# mapleCUx_large_400-001.net
KiCad netlist of a schematic drawn in EAGLE
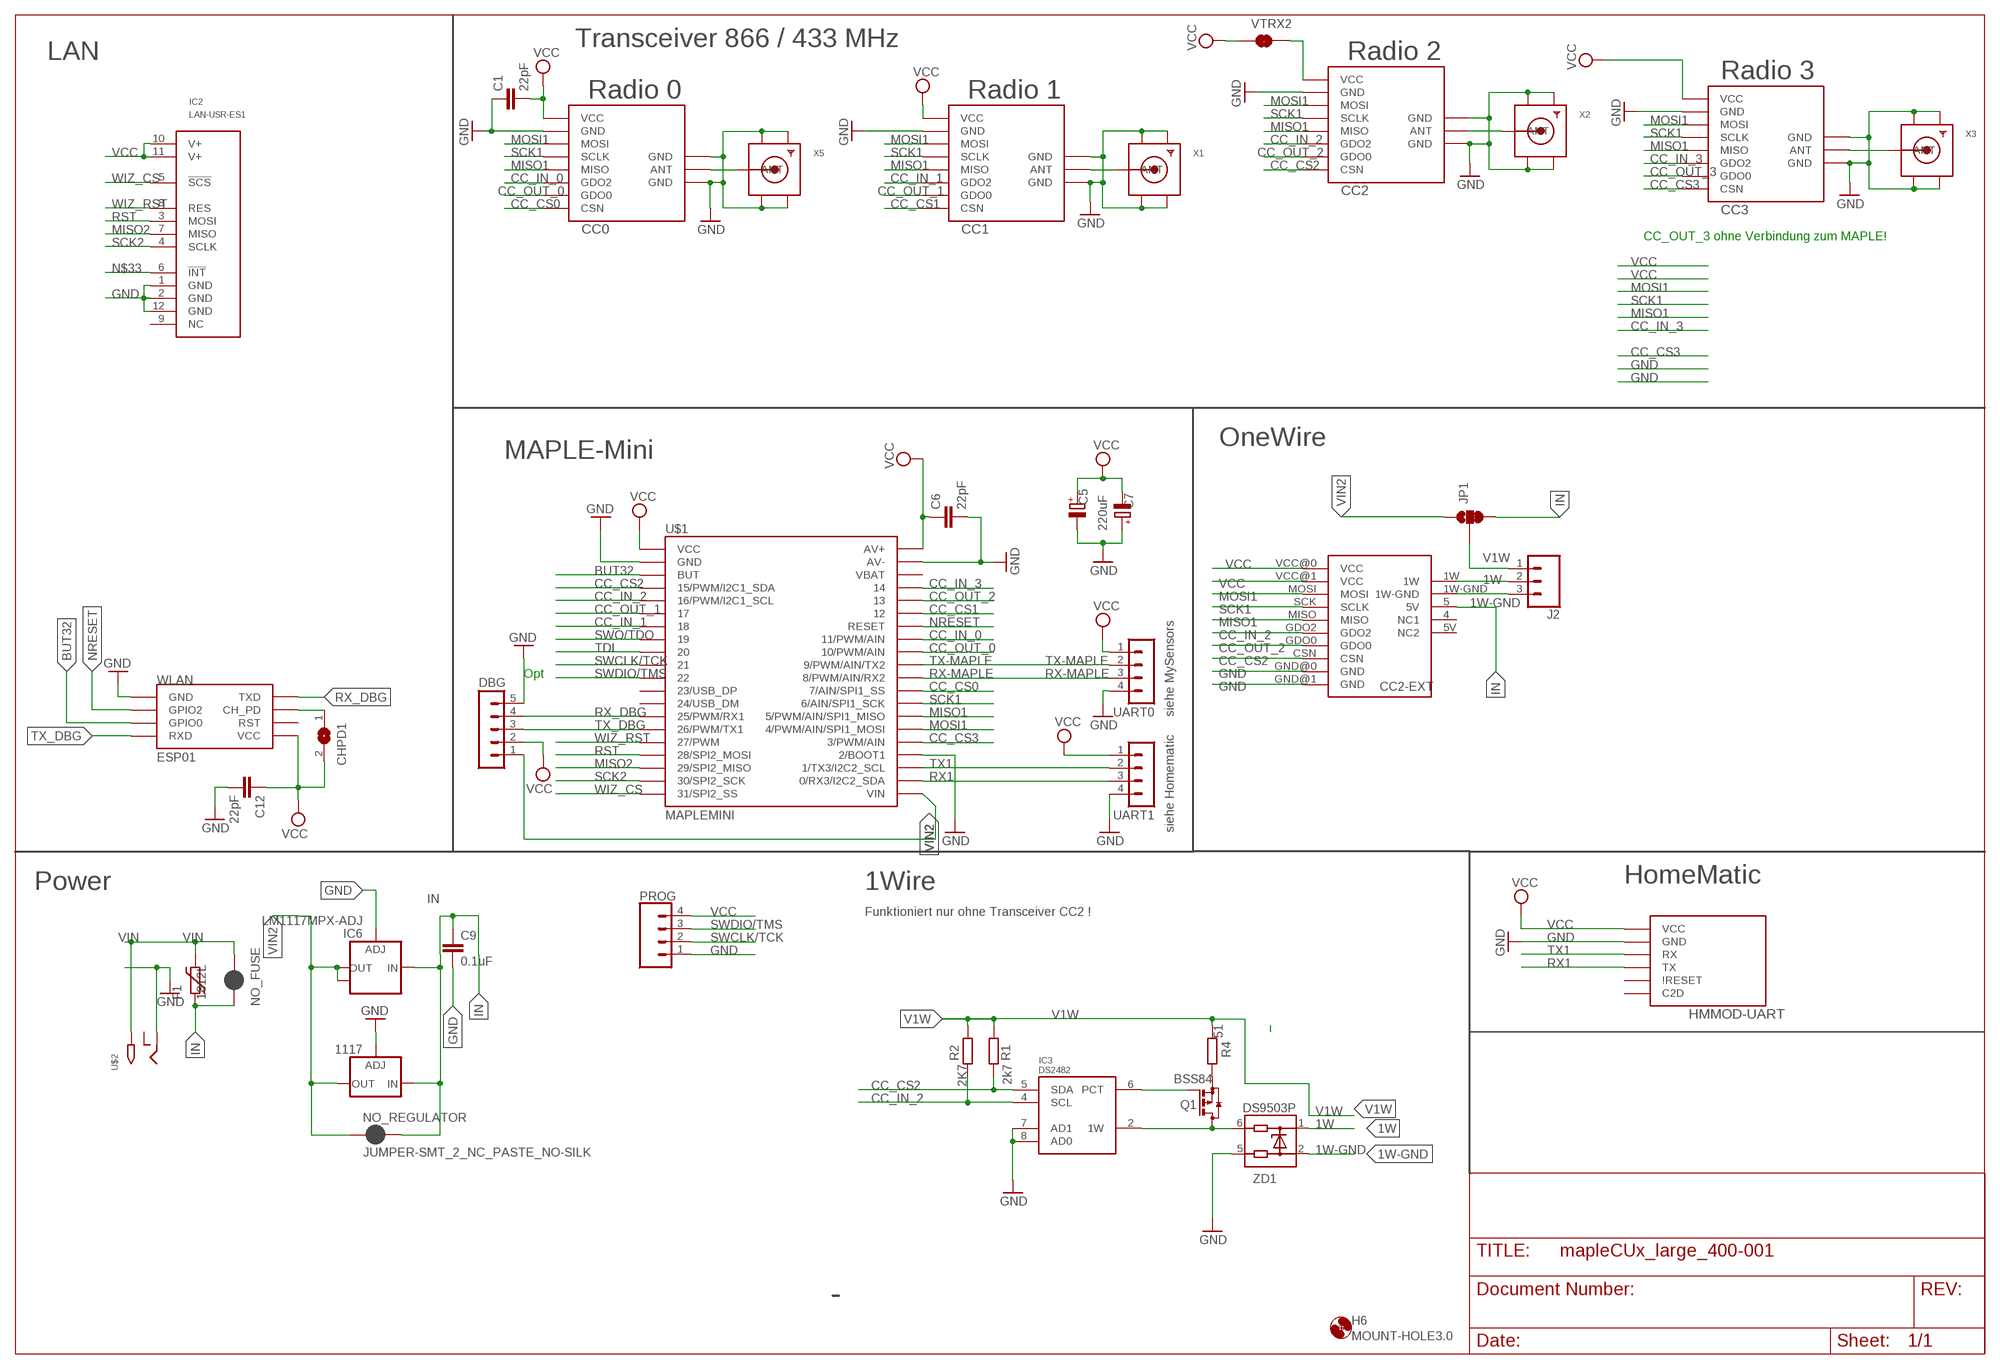
[diagram p0: schematic, sheet 1]

(export (version "E")
  (design (tool "Eeschema 10.0.6"))
  (components
    (comp (ref "1117")
      (value "LD117ADT50TR")
      (footprint "eagle-import:DPACK")
      (libsource (lib "eagle-import") (part "LD117A?DT50TR"))
    )
    (comp (ref "C1")
      (value "22pF")
      (footprint "eagle-import:C0805")
      (libsource (lib "eagle-import") (part "C-EUC0805"))
    )
    (comp (ref "C5")
      (value "220uF")
      (footprint "eagle-import:E5-8,5")
      (libsource (lib "eagle-import") (part "CPOL-EUE5-8.5"))
    )
    (comp (ref "C6")
      (value "22pF")
      (footprint "eagle-import:C0805")
      (libsource (lib "eagle-import") (part "C-EUC0805"))
    )
    (comp (ref "C7")
      (value "CPOL-EUSMCE")
      (footprint "eagle-import:SMC_E")
      (libsource (lib "eagle-import") (part "rcl_334_CPOL-EUSMCE"))
    )
    (comp (ref "C9")
      (value "0.1uF")
      (footprint "eagle-import:C1206")
      (libsource (lib "eagle-import") (part "C-EUC1206"))
    )
    (comp (ref "C12")
      (value "22pF")
      (footprint "eagle-import:C0805")
      (libsource (lib "eagle-import") (part "C-EUC0805"))
    )
    (comp (ref "CC0")
      (value "CC1101")
      (footprint "eagle-import:CC1101_MODULE1_SMD")
      (libsource (lib "eagle-import") (part "CC1101_MODULE1SMD"))
    )
    (comp (ref "CC1")
      (value "CC1101_MODULE1SMD")
      (footprint "eagle-import:CC1101_MODULE1_SMD")
      (libsource (lib "eagle-import") (part "CC1101_MODULE1SMD"))
    )
    (comp (ref "CC2")
      (value "CC1101_MODULE1SMD")
      (footprint "eagle-import:CC1101_MODULE1_SMD")
      (libsource (lib "eagle-import") (part "CC1101_MODULE1SMD"))
    )
    (comp (ref "CC2-EXT")
      (value "ONEWIRE-MODULE")
      (footprint "eagle-import:ONEWIRE_CC1101_MODULE3_DIL")
      (libsource (lib "eagle-import") (part "ONEWIRE-MODULE"))
    )
    (comp (ref "CC3")
      (value "CC1101_MODULE1SMD")
      (footprint "eagle-import:CC1101_MODULE1_SMD")
      (libsource (lib "eagle-import") (part "CC1101_MODULE1SMD"))
    )
    (comp (ref "CHPD1")
      (value "SJ")
      (footprint "eagle-import:SJ")
      (libsource (lib "eagle-import") (part "SJ"))
    )
    (comp (ref "DBG")
      (value "MA05-1")
      (footprint "eagle-import:MA05-1")
      (libsource (lib "eagle-import") (part "MA05-1"))
    )
    (comp (ref "F1")
      (value "1812L")
      (footprint "eagle-import:1812L")
      (libsource (lib "eagle-import") (part "1812L"))
    )
    (comp (ref "H6")
      (value "MOUNT-HOLE3.0")
      (footprint "eagle-import:3,0")
      (libsource (lib "eagle-import") (part "MOUNT-HOLE3.0"))
    )
    (comp (ref "HMMOD-UART")
      (value "HM-MOD-UARTDIL")
      (footprint "eagle-import:HM-MOD-UART-DIL")
      (libsource (lib "eagle-import") (part "HM-MOD-UARTDIL"))
    )
    (comp (ref "IC2")
      (value "LAN-USR-ES1")
      (footprint "eagle-import:USR-ES1")
      (libsource (lib "eagle-import") (part "LAN-USR-ES1"))
    )
    (comp (ref "IC3")
      (value "DS2482")
      (footprint "eagle-import:SO08")
      (libsource (lib "eagle-import") (part "DS2482-100S"))
    )
    (comp (ref "IC6")
      (value "LM1117MPX-ADJ")
      (footprint "eagle-import:SOT223")
      (libsource (lib "eagle-import") (part "LM1117MPX-ADJ"))
    )
    (comp (ref "J2")
      (value "CONN_03LONGPADS")
      (footprint "eagle-import:1X03_LONGPADS")
      (libsource (lib "eagle-import") (part "CONN_03LONGPADS"))
    )
    (comp (ref "JP1")
      (value "JUMPER-SMT_3_1-NC_TRACE_SILK")
      (footprint "eagle-import:SMT-JUMPER_3_1-NC_TRACE_SILK")
      (libsource (lib "eagle-import") (part "JUMPER-SMT_3_1-NC_TRACE_SILK"))
    )
    (comp (ref "NO_FUSE")
      (value "JUMPER-SMT_2_NC_PASTE_NO-SILK")
      (footprint "eagle-import:SMT-JUMPER_2_NC_PASTE_NO-SILK")
      (libsource (lib "eagle-import") (part "JUMPER-SMT_2_NC_PASTE_NO-SILK"))
    )
    (comp (ref "NO_REGULATOR")
      (value "JUMPER-SMT_2_NC_PASTE_NO-SILK")
      (footprint "eagle-import:SMT-JUMPER_2_NC_PASTE_NO-SILK")
      (libsource (lib "eagle-import") (part "JUMPER-SMT_2_NC_PASTE_NO-SILK"))
    )
    (comp (ref "PROG")
      (value "CONN_04LOCK")
      (footprint "eagle-import:1X04_LOCK")
      (libsource (lib "eagle-import") (part "CONN_04LOCK"))
    )
    (comp (ref "Q1")
      (value "BSS84")
      (footprint "eagle-import:SOT23")
      (libsource (lib "eagle-import") (part "BSS84"))
    )
    (comp (ref "R1")
      (value "2k7")
      (footprint "eagle-import:R0805")
      (libsource (lib "eagle-import") (part "R-EU_R0805"))
    )
    (comp (ref "R2")
      (value "2K7")
      (footprint "eagle-import:R0805")
      (libsource (lib "eagle-import") (part "R-EU_R0805"))
    )
    (comp (ref "R4")
      (value "51")
      (footprint "eagle-import:R0805")
      (libsource (lib "eagle-import") (part "R-EU_R0805"))
    )
    (comp (ref "U$1")
      (value "MAPLEMINI")
      (footprint "eagle-import:20-DIP")
      (libsource (lib "eagle-import") (part "MAPLEMINI"))
    )
    (comp (ref "U$2")
      (value "2.1MMJACKTHM")
      (footprint "eagle-import:PJ-102A")
      (libsource (lib "eagle-import") (part "2.1MMJACKTHM"))
    )
    (comp (ref "UART0")
      (value "MA04-1")
      (footprint "eagle-import:MA04-1")
      (libsource (lib "eagle-import") (part "MA04-1"))
    )
    (comp (ref "UART1")
      (value "MA04-1")
      (footprint "eagle-import:MA04-1")
      (libsource (lib "eagle-import") (part "MA04-1"))
    )
    (comp (ref "VTRX2")
      (value "JUMPER-SMT_2_NC_TRACE_SILK")
      (footprint "eagle-import:SMT-JUMPER_2_NC_TRACE_SILK")
      (libsource (lib "eagle-import") (part "JUMPER-SMT_2_NC_TRACE_SILK"))
    )
    (comp (ref "WLAN")
      (value "ESP01")
      (footprint "eagle-import:ESP01")
      (libsource (lib "eagle-import") (part "ESP01"))
    )
    (comp (ref "X1")
      (value "SMACONNECTOR_EDGE")
      (footprint "eagle-import:SMA_EDGELAUNCH")
      (libsource (lib "eagle-import") (part "SMACONNECTOR_EDGE"))
    )
    (comp (ref "X2")
      (value "SMACONNECTOR_EDGE")
      (footprint "eagle-import:SMA_EDGELAUNCH")
      (libsource (lib "eagle-import") (part "SMACONNECTOR_EDGE"))
    )
    (comp (ref "X3")
      (value "SMACONNECTOR_EDGE")
      (footprint "eagle-import:SMA_EDGELAUNCH")
      (libsource (lib "eagle-import") (part "SMACONNECTOR_EDGE"))
    )
    (comp (ref "X5")
      (value "SMACONNECTOR_EDGE")
      (footprint "eagle-import:SMA_EDGELAUNCH")
      (libsource (lib "eagle-import") (part "SMACONNECTOR_EDGE"))
    )
    (comp (ref "ZD1")
      (value "DS9503P")
      (footprint "eagle-import:TSOC6")
      (libsource (lib "eagle-import") (part "DS9503P"))
    )
  )
  (nets
    (net (code "1") (name "/CC_CS0") (class "Default")
      (node (ref "CC0") (pin "CSN") (pinfunction "CSN_CSN") (pintype "bidirectional"))
      (node (ref "U$1") (pin "29") (pinfunction "7/AIN/SPI1_SS_29") (pintype "bidirectional"))
    )
    (net (code "2") (name "/CC_CS1") (class "Default")
      (node (ref "CC1") (pin "CSN") (pinfunction "CSN_CSN") (pintype "bidirectional"))
      (node (ref "U$1") (pin "35") (pinfunction "12_35") (pintype "bidirectional"))
    )
    (net (code "3") (name "/CC_CS2") (class "Default")
      (node (ref "CC2") (pin "CSN") (pinfunction "CSN_CSN") (pintype "bidirectional"))
      (node (ref "CC2-EXT") (pin "CSN") (pinfunction "CSN_CSN") (pintype "bidirectional"))
      (node (ref "IC3") (pin "5") (pinfunction "SDA_5") (pintype "bidirectional"))
      (node (ref "R1") (pin "2") (pinfunction "2_2") (pintype "passive"))
      (node (ref "U$1") (pin "4") (pinfunction "15/PWM/I2C1_SDA_4") (pintype "bidirectional"))
    )
    (net (code "4") (name "/CC_CS3") (class "Default")
      (node (ref "CC3") (pin "CSN") (pinfunction "CSN_CSN") (pintype "bidirectional"))
      (node (ref "U$1") (pin "25") (pinfunction "3/PWM/AIN_25") (pintype "bidirectional"))
    )
    (net (code "5") (name "/CC_IN_0") (class "Default")
      (node (ref "CC0") (pin "GDO2") (pinfunction "GDO2_GDO2") (pintype "bidirectional"))
      (node (ref "U$1") (pin "33") (pinfunction "11/PWM/AIN_33") (pintype "bidirectional"))
    )
    (net (code "6") (name "/CC_IN_1") (class "Default")
      (node (ref "CC1") (pin "GDO2") (pinfunction "GDO2_GDO2") (pintype "bidirectional"))
      (node (ref "U$1") (pin "7") (pinfunction "18_7") (pintype "bidirectional"))
    )
    (net (code "7") (name "/CC_IN_2") (class "Default")
      (node (ref "CC2") (pin "GDO2") (pinfunction "GDO2_GDO2") (pintype "bidirectional"))
      (node (ref "CC2-EXT") (pin "GDO2") (pinfunction "GDO2_GDO2") (pintype "bidirectional"))
      (node (ref "IC3") (pin "4") (pinfunction "SCL_4") (pintype "input"))
      (node (ref "R2") (pin "2") (pinfunction "2_2") (pintype "passive"))
      (node (ref "U$1") (pin "5") (pinfunction "16/PWM/I2C1_SCL_5") (pintype "bidirectional"))
    )
    (net (code "8") (name "/CC_IN_3") (class "Default")
      (node (ref "CC3") (pin "GDO2") (pinfunction "GDO2_GDO2") (pintype "bidirectional"))
      (node (ref "U$1") (pin "37") (pinfunction "14_37") (pintype "bidirectional"))
    )
    (net (code "9") (name "/CC_OUT_0") (class "Default")
      (node (ref "CC0") (pin "GDO0") (pinfunction "GDO0_GDO0") (pintype "bidirectional"))
      (node (ref "U$1") (pin "32") (pinfunction "10/PWM/AIN_32") (pintype "bidirectional"))
    )
    (net (code "10") (name "/CC_OUT_1") (class "Default")
      (node (ref "CC1") (pin "GDO0") (pinfunction "GDO0_GDO0") (pintype "bidirectional"))
      (node (ref "U$1") (pin "6") (pinfunction "17_6") (pintype "bidirectional"))
    )
    (net (code "11") (name "/CC_OUT_2") (class "Default")
      (node (ref "CC2") (pin "GDO0") (pinfunction "GDO0_GDO0") (pintype "bidirectional"))
      (node (ref "CC2-EXT") (pin "GDO0") (pinfunction "GDO0_GDO0") (pintype "bidirectional"))
      (node (ref "U$1") (pin "36") (pinfunction "13_36") (pintype "bidirectional"))
    )
    (net (code "12") (name "/CC_OUT_3") (class "Default")
      (node (ref "CC3") (pin "GDO0") (pinfunction "GDO0_GDO0") (pintype "bidirectional"))
    )
    (net (code "13") (name "/MISO1") (class "Default")
      (node (ref "CC0") (pin "MISO") (pinfunction "MISO_MISO") (pintype "bidirectional"))
      (node (ref "CC1") (pin "MISO") (pinfunction "MISO_MISO") (pintype "bidirectional"))
      (node (ref "CC2") (pin "MISO") (pinfunction "MISO_MISO") (pintype "bidirectional"))
      (node (ref "CC2-EXT") (pin "MISO") (pinfunction "MISO_MISO") (pintype "bidirectional"))
      (node (ref "CC3") (pin "MISO") (pinfunction "MISO_MISO") (pintype "bidirectional"))
      (node (ref "U$1") (pin "27") (pinfunction "5/PWM/AIN/SPI1_MISO_27") (pintype "bidirectional"))
    )
    (net (code "14") (name "/MISO2") (class "Default")
      (node (ref "IC2") (pin "7") (pinfunction "MISO_7") (pintype "bidirectional"))
      (node (ref "U$1") (pin "18") (pinfunction "29/SPI2_MISO_18") (pintype "bidirectional"))
    )
    (net (code "15") (name "/MOSI1") (class "Default")
      (node (ref "CC0") (pin "MOSI") (pinfunction "MOSI_MOSI") (pintype "bidirectional"))
      (node (ref "CC1") (pin "MOSI") (pinfunction "MOSI_MOSI") (pintype "bidirectional"))
      (node (ref "CC2") (pin "MOSI") (pinfunction "MOSI_MOSI") (pintype "bidirectional"))
      (node (ref "CC2-EXT") (pin "MOSI") (pinfunction "MOSI_MOSI") (pintype "bidirectional"))
      (node (ref "CC3") (pin "MOSI") (pinfunction "MOSI_MOSI") (pintype "bidirectional"))
      (node (ref "U$1") (pin "26") (pinfunction "4/PWM/AIN/SPI1_MOSI_26") (pintype "bidirectional"))
    )
    (net (code "16") (name "/N$33") (class "Default")
      (node (ref "IC2") (pin "6") (pinfunction "~{INT}_6") (pintype "output"))
    )
    (net (code "17") (name "/RST") (class "Default")
      (node (ref "IC2") (pin "3") (pinfunction "MOSI_3") (pintype "bidirectional"))
      (node (ref "U$1") (pin "17") (pinfunction "28/SPI2_MOSI_17") (pintype "bidirectional"))
    )
    (net (code "18") (name "/RX-MAPLE") (class "Default")
      (node (ref "U$1") (pin "30") (pinfunction "8/PWM/AIN/RX2_30") (pintype "bidirectional"))
      (node (ref "UART0") (pin "3") (pinfunction "3_3") (pintype "passive"))
    )
    (net (code "19") (name "/RX1") (class "Default")
      (node (ref "HMMOD-UART") (pin "5") (pinfunction "TX_5") (pintype "bidirectional"))
      (node (ref "U$1") (pin "22") (pinfunction "0/RX3/I2C2_SDA_22") (pintype "bidirectional"))
      (node (ref "UART1") (pin "3") (pinfunction "3_3") (pintype "passive"))
    )
    (net (code "20") (name "/SCK1") (class "Default")
      (node (ref "CC0") (pin "SCLK") (pinfunction "SCLK_SCLK") (pintype "bidirectional"))
      (node (ref "CC1") (pin "SCLK") (pinfunction "SCLK_SCLK") (pintype "bidirectional"))
      (node (ref "CC2") (pin "SCLK") (pinfunction "SCLK_SCLK") (pintype "bidirectional"))
      (node (ref "CC2-EXT") (pin "SCK") (pinfunction "SCLK_SCK") (pintype "bidirectional"))
      (node (ref "CC3") (pin "SCLK") (pinfunction "SCLK_SCLK") (pintype "bidirectional"))
      (node (ref "U$1") (pin "28") (pinfunction "6/AIN/SPI1_SCK_28") (pintype "bidirectional"))
    )
    (net (code "21") (name "/SCK2") (class "Default")
      (node (ref "IC2") (pin "4") (pinfunction "SCLK_4") (pintype "input"))
      (node (ref "U$1") (pin "19") (pinfunction "30/SPI2_SCK_19") (pintype "bidirectional"))
    )
    (net (code "22") (name "/SWCLK{slash}TCK") (class "Default")
      (node (ref "PROG") (pin "2") (pinfunction "2_2") (pintype "passive"))
      (node (ref "U$1") (pin "10") (pinfunction "21_10") (pintype "bidirectional"))
    )
    (net (code "23") (name "/SWDIO{slash}TMS") (class "Default")
      (node (ref "PROG") (pin "3") (pinfunction "3_3") (pintype "passive"))
      (node (ref "U$1") (pin "11") (pinfunction "22_11") (pintype "bidirectional"))
    )
    (net (code "24") (name "/SWO{slash}TDO") (class "Default")
      (node (ref "U$1") (pin "8") (pinfunction "19_8") (pintype "bidirectional"))
    )
    (net (code "25") (name "/TDI") (class "Default")
      (node (ref "U$1") (pin "9") (pinfunction "20_9") (pintype "bidirectional"))
    )
    (net (code "26") (name "/TX-MAPLE") (class "Default")
      (node (ref "U$1") (pin "31") (pinfunction "9/PWM/AIN/TX2_31") (pintype "bidirectional"))
      (node (ref "UART0") (pin "2") (pinfunction "2_2") (pintype "passive"))
    )
    (net (code "27") (name "/TX1") (class "Default")
      (node (ref "HMMOD-UART") (pin "6") (pinfunction "RX_6") (pintype "bidirectional"))
      (node (ref "U$1") (pin "23") (pinfunction "1/TX3/I2C2_SCL_23") (pintype "bidirectional"))
      (node (ref "UART1") (pin "2") (pinfunction "2_2") (pintype "passive"))
    )
    (net (code "28") (name "/VIN") (class "Default")
      (node (ref "F1") (pin "P$2") (pinfunction "2_P$2") (pintype "passive"))
      (node (ref "NO_FUSE") (pin "2") (pinfunction "2_2") (pintype "passive"))
      (node (ref "U$2") (pin "TIP") (pinfunction "TIP_TIP") (pintype "bidirectional"))
    )
    (net (code "29") (name "/WIZ_CS") (class "Default")
      (node (ref "IC2") (pin "5") (pinfunction "~{SCS}_5") (pintype "input"))
      (node (ref "U$1") (pin "20") (pinfunction "31/SPI2_SS_20") (pintype "bidirectional"))
    )
    (net (code "30") (name "/WIZ_RST") (class "Default")
      (node (ref "IC2") (pin "8") (pinfunction "RES_8") (pintype "input"))
      (node (ref "U$1") (pin "16") (pinfunction "27/PWM_16") (pintype "bidirectional"))
    )
    (net (code "31") (name "1W") (class "Default")
      (node (ref "CC2-EXT") (pin "1W") (pinfunction "1W_1W") (pintype "bidirectional"))
      (node (ref "J2") (pin "2") (pinfunction "2_2") (pintype "passive"))
      (node (ref "ZD1") (pin "1") (pinfunction "P$1_1") (pintype "passive"))
    )
    (net (code "32") (name "1W-GND") (class "Default")
      (node (ref "CC2-EXT") (pin "1W-GND") (pinfunction "1W-GND_1W-GND") (pintype "bidirectional"))
      (node (ref "J2") (pin "3") (pinfunction "3_3") (pintype "passive"))
      (node (ref "ZD1") (pin "2") (pinfunction "P$2_2") (pintype "passive"))
    )
    (net (code "33") (name "BUT32") (class "Default")
      (node (ref "U$1") (pin "3") (pinfunction "BUT_3") (pintype "bidirectional"))
      (node (ref "WLAN") (pin "GPIO0") (pinfunction "GPIO0_GPIO0") (pintype "bidirectional"))
    )
    (net (code "34") (name "GND") (class "Default")
      (node (ref "1117") (pin "1") (pinfunction "ADJ_1") (pintype "input"))
      (node (ref "C1") (pin "1") (pinfunction "1_1") (pintype "passive"))
      (node (ref "C12") (pin "2") (pinfunction "2_2") (pintype "passive"))
      (node (ref "C5") (pin "-") (pinfunction "-_-") (pintype "passive"))
      (node (ref "C6") (pin "2") (pinfunction "2_2") (pintype "passive"))
      (node (ref "C7") (pin "+") (pinfunction "+_+") (pintype "passive"))
      (node (ref "C9") (pin "2") (pinfunction "2_2") (pintype "passive"))
      (node (ref "CC0") (pin "GND@0") (pinfunction "GND_GND@0") (pintype "power_in"))
      (node (ref "CC0") (pin "GND@1") (pinfunction "GND_GND@1") (pintype "power_in"))
      (node (ref "CC0") (pin "GND@2") (pinfunction "GND_GND@2") (pintype "power_in"))
      (node (ref "CC1") (pin "GND@0") (pinfunction "GND_GND@0") (pintype "power_in"))
      (node (ref "CC1") (pin "GND@1") (pinfunction "GND_GND@1") (pintype "power_in"))
      (node (ref "CC1") (pin "GND@2") (pinfunction "GND_GND@2") (pintype "power_in"))
      (node (ref "CC2") (pin "GND@0") (pinfunction "GND_GND@0") (pintype "power_in"))
      (node (ref "CC2") (pin "GND@1") (pinfunction "GND_GND@1") (pintype "power_in"))
      (node (ref "CC2") (pin "GND@2") (pinfunction "GND_GND@2") (pintype "power_in"))
      (node (ref "CC2-EXT") (pin "GND@0") (pinfunction "GND_GND@0") (pintype "power_in"))
      (node (ref "CC2-EXT") (pin "GND@1") (pinfunction "GND_GND@1") (pintype "power_in"))
      (node (ref "CC3") (pin "GND@0") (pinfunction "GND_GND@0") (pintype "power_in"))
      (node (ref "CC3") (pin "GND@1") (pinfunction "GND_GND@1") (pintype "power_in"))
      (node (ref "CC3") (pin "GND@2") (pinfunction "GND_GND@2") (pintype "power_in"))
      (node (ref "DBG") (pin "5") (pinfunction "5_5") (pintype "passive"))
      (node (ref "HMMOD-UART") (pin "2") (pinfunction "GND_2") (pintype "power_in"))
      (node (ref "IC2") (pin "1") (pinfunction "GND_1") (pintype "power_in"))
      (node (ref "IC2") (pin "12") (pinfunction "GND_12") (pintype "power_in"))
      (node (ref "IC2") (pin "2") (pinfunction "GND_2") (pintype "power_in"))
      (node (ref "IC3") (pin "7") (pinfunction "AD1_7") (pintype "input"))
      (node (ref "IC3") (pin "8") (pinfunction "AD0_8") (pintype "input"))
      (node (ref "IC6") (pin "1") (pinfunction "ADJ_1") (pintype "input"))
      (node (ref "PROG") (pin "1") (pinfunction "1_1") (pintype "passive"))
      (node (ref "U$1") (pin "2") (pinfunction "GND_2") (pintype "bidirectional"))
      (node (ref "U$1") (pin "24") (pinfunction "2/BOOT1_24") (pintype "bidirectional"))
      (node (ref "U$1") (pin "39") (pinfunction "AV-_39") (pintype "bidirectional"))
      (node (ref "U$2") (pin "RING") (pinfunction "RING_RING") (pintype "bidirectional"))
      (node (ref "UART0") (pin "4") (pinfunction "4_4") (pintype "passive"))
      (node (ref "UART1") (pin "4") (pinfunction "4_4") (pintype "passive"))
      (node (ref "WLAN") (pin "GND") (pinfunction "GND_GND") (pintype "bidirectional"))
      (node (ref "X1") (pin "GND@1") (pinfunction "GND4_GND@1") (pintype "power_in"))
      (node (ref "X1") (pin "GND@2") (pinfunction "GND3_GND@2") (pintype "power_in"))
      (node (ref "X1") (pin "GND@3") (pinfunction "GND2_GND@3") (pintype "power_in"))
      (node (ref "X1") (pin "GND@4") (pinfunction "GND1_GND@4") (pintype "power_in"))
      (node (ref "X2") (pin "GND@1") (pinfunction "GND4_GND@1") (pintype "power_in"))
      (node (ref "X2") (pin "GND@2") (pinfunction "GND3_GND@2") (pintype "power_in"))
      (node (ref "X2") (pin "GND@3") (pinfunction "GND2_GND@3") (pintype "power_in"))
      (node (ref "X2") (pin "GND@4") (pinfunction "GND1_GND@4") (pintype "power_in"))
      (node (ref "X3") (pin "GND@1") (pinfunction "GND4_GND@1") (pintype "power_in"))
      (node (ref "X3") (pin "GND@2") (pinfunction "GND3_GND@2") (pintype "power_in"))
      (node (ref "X3") (pin "GND@3") (pinfunction "GND2_GND@3") (pintype "power_in"))
      (node (ref "X3") (pin "GND@4") (pinfunction "GND1_GND@4") (pintype "power_in"))
      (node (ref "X5") (pin "GND@1") (pinfunction "GND4_GND@1") (pintype "power_in"))
      (node (ref "X5") (pin "GND@2") (pinfunction "GND3_GND@2") (pintype "power_in"))
      (node (ref "X5") (pin "GND@3") (pinfunction "GND2_GND@3") (pintype "power_in"))
      (node (ref "X5") (pin "GND@4") (pinfunction "GND1_GND@4") (pintype "power_in"))
      (node (ref "ZD1") (pin "5") (pinfunction "P$3_5") (pintype "passive"))
    )
    (net (code "35") (name "IN") (class "Default")
      (node (ref "1117") (pin "3") (pinfunction "IN_3") (pintype "input"))
      (node (ref "C9") (pin "1") (pinfunction "1_1") (pintype "passive"))
      (node (ref "CC2-EXT") (pin "5") (pinfunction "5V_5") (pintype "bidirectional"))
      (node (ref "F1") (pin "P$1") (pinfunction "1_P$1") (pintype "passive"))
      (node (ref "IC6") (pin "3") (pinfunction "IN_3") (pintype "input"))
      (node (ref "JP1") (pin "3") (pinfunction "3_3") (pintype "passive"))
      (node (ref "NO_FUSE") (pin "1") (pinfunction "1_1") (pintype "passive"))
      (node (ref "NO_REGULATOR") (pin "2") (pinfunction "2_2") (pintype "passive"))
    )
    (net (code "36") (name "NRESET") (class "Default")
      (node (ref "U$1") (pin "34") (pinfunction "RESET_34") (pintype "bidirectional"))
      (node (ref "WLAN") (pin "GPIO2") (pinfunction "GPIO2_GPIO2") (pintype "bidirectional"))
    )
    (net (code "37") (name "Net-(CC2-PadVCC)") (class "Default")
      (node (ref "CC2") (pin "VCC") (pinfunction "VCC_VCC") (pintype "power_in"))
      (node (ref "VTRX2") (pin "2") (pinfunction "2_2") (pintype "passive"))
    )
    (net (code "38") (name "Net-(CHPD1-Pad1)") (class "Default")
      (node (ref "CHPD1") (pin "1") (pinfunction "1_1") (pintype "passive"))
      (node (ref "WLAN") (pin "CH_PD") (pinfunction "CH_PD_CH_PD") (pintype "bidirectional"))
    )
    (net (code "39") (name "Net-(IC3A-1W)") (class "Default")
      (node (ref "IC3") (pin "2") (pinfunction "1W_2") (pintype "open_collector"))
      (node (ref "Q1") (pin "3") (pinfunction "D_3") (pintype "passive"))
      (node (ref "ZD1") (pin "6") (pinfunction "P$4_6") (pintype "passive"))
    )
    (net (code "40") (name "Net-(IC3A-PCT)") (class "Default")
      (node (ref "IC3") (pin "6") (pinfunction "PCT_6") (pintype "output"))
      (node (ref "Q1") (pin "1") (pinfunction "G_1") (pintype "passive"))
    )
    (net (code "41") (name "Net-(Q1-S)") (class "Default")
      (node (ref "Q1") (pin "2") (pinfunction "S_2") (pintype "passive"))
      (node (ref "R4") (pin "1") (pinfunction "1_1") (pintype "passive"))
    )
    (net (code "42") (name "Net-(X1-ANT)") (class "Default")
      (node (ref "CC1") (pin "ANT") (pinfunction "ANT_ANT") (pintype "output"))
      (node (ref "X1") (pin "P") (pinfunction "ANT_P") (pintype "bidirectional"))
    )
    (net (code "43") (name "Net-(X2-ANT)") (class "Default")
      (node (ref "CC2") (pin "ANT") (pinfunction "ANT_ANT") (pintype "output"))
      (node (ref "X2") (pin "P") (pinfunction "ANT_P") (pintype "bidirectional"))
    )
    (net (code "44") (name "Net-(X3-ANT)") (class "Default")
      (node (ref "CC3") (pin "ANT") (pinfunction "ANT_ANT") (pintype "output"))
      (node (ref "X3") (pin "P") (pinfunction "ANT_P") (pintype "bidirectional"))
    )
    (net (code "45") (name "Net-(X5-ANT)") (class "Default")
      (node (ref "CC0") (pin "ANT") (pinfunction "ANT_ANT") (pintype "output"))
      (node (ref "X5") (pin "P") (pinfunction "ANT_P") (pintype "bidirectional"))
    )
    (net (code "46") (name "RX_DBG") (class "Default")
      (node (ref "DBG") (pin "4") (pinfunction "4_4") (pintype "passive"))
      (node (ref "U$1") (pin "14") (pinfunction "25/PWM/RX1_14") (pintype "bidirectional"))
      (node (ref "WLAN") (pin "TX") (pinfunction "TXD_TX") (pintype "bidirectional"))
    )
    (net (code "47") (name "TX_DBG") (class "Default")
      (node (ref "DBG") (pin "3") (pinfunction "3_3") (pintype "passive"))
      (node (ref "U$1") (pin "15") (pinfunction "26/PWM/TX1_15") (pintype "bidirectional"))
      (node (ref "WLAN") (pin "RX") (pinfunction "RXD_RX") (pintype "bidirectional"))
    )
    (net (code "48") (name "V1W") (class "Default")
      (node (ref "J2") (pin "1") (pinfunction "1_1") (pintype "passive"))
      (node (ref "JP1") (pin "2") (pinfunction "2_2") (pintype "passive"))
      (node (ref "R1") (pin "1") (pinfunction "1_1") (pintype "passive"))
      (node (ref "R2") (pin "1") (pinfunction "1_1") (pintype "passive"))
      (node (ref "R4") (pin "2") (pinfunction "2_2") (pintype "passive"))
    )
    (net (code "49") (name "VCC") (class "Default")
      (node (ref "C1") (pin "2") (pinfunction "2_2") (pintype "passive"))
      (node (ref "C12") (pin "1") (pinfunction "1_1") (pintype "passive"))
      (node (ref "C5") (pin "+") (pinfunction "+_+") (pintype "passive"))
      (node (ref "C6") (pin "1") (pinfunction "1_1") (pintype "passive"))
      (node (ref "C7") (pin "-") (pinfunction "-_-") (pintype "passive"))
      (node (ref "CC0") (pin "VCC") (pinfunction "VCC_VCC") (pintype "power_in"))
      (node (ref "CC1") (pin "VCC") (pinfunction "VCC_VCC") (pintype "power_in"))
      (node (ref "CC2-EXT") (pin "VCC@0") (pinfunction "VCC_VCC@0") (pintype "power_in"))
      (node (ref "CC2-EXT") (pin "VCC@1") (pinfunction "VCC_VCC@1") (pintype "power_in"))
      (node (ref "CC3") (pin "VCC") (pinfunction "VCC_VCC") (pintype "power_in"))
      (node (ref "CHPD1") (pin "2") (pinfunction "2_2") (pintype "passive"))
      (node (ref "DBG") (pin "2") (pinfunction "2_2") (pintype "passive"))
      (node (ref "HMMOD-UART") (pin "1") (pinfunction "VCC_1") (pintype "power_in"))
      (node (ref "IC2") (pin "10") (pinfunction "V+_10") (pintype "power_in"))
      (node (ref "IC2") (pin "11") (pinfunction "V+_11") (pintype "power_in"))
      (node (ref "PROG") (pin "4") (pinfunction "4_4") (pintype "passive"))
      (node (ref "U$1") (pin "1") (pinfunction "VCC_1") (pintype "bidirectional"))
      (node (ref "U$1") (pin "40") (pinfunction "AV+_40") (pintype "bidirectional"))
      (node (ref "UART0") (pin "1") (pinfunction "1_1") (pintype "passive"))
      (node (ref "UART1") (pin "1") (pinfunction "1_1") (pintype "passive"))
      (node (ref "VTRX2") (pin "1") (pinfunction "1_1") (pintype "passive"))
      (node (ref "WLAN") (pin "VCC") (pinfunction "VCC_VCC") (pintype "bidirectional"))
    )
    (net (code "50") (name "VIN2") (class "Default")
      (node (ref "1117") (pin "4") (pinfunction "OUT_4") (pintype "passive"))
      (node (ref "DBG") (pin "1") (pinfunction "1_1") (pintype "passive"))
      (node (ref "IC6") (pin "2") (pinfunction "OUT_2") (pintype "passive"))
      (node (ref "IC6") (pin "TAB") (pinfunction "OUT1_TAB") (pintype "passive"))
      (node (ref "JP1") (pin "1") (pinfunction "1_1") (pintype "passive"))
      (node (ref "NO_REGULATOR") (pin "1") (pinfunction "1_1") (pintype "passive"))
      (node (ref "U$1") (pin "21") (pinfunction "VIN_21") (pintype "bidirectional"))
    )
    (net (code "51") (name "unconnected-(CC2-EXT-NC1-Pad4)") (class "Default")
      (node (ref "CC2-EXT") (pin "4") (pinfunction "NC1_4") (pintype "bidirectional"))
    )
    (net (code "52") (name "unconnected-(CC2-EXT-NC2-Pad5V)") (class "Default")
      (node (ref "CC2-EXT") (pin "5V") (pinfunction "NC2_5V") (pintype "bidirectional"))
    )
    (net (code "53") (name "unconnected-(HMMOD-UART-C2D-Pad3)") (class "Default")
      (node (ref "HMMOD-UART") (pin "3") (pinfunction "C2D_3") (pintype "bidirectional"))
    )
    (net (code "54") (name "unconnected-(HMMOD-UART-\\~{RESET}-Pad4)") (class "Default")
      (node (ref "HMMOD-UART") (pin "4") (pinfunction "\\~{RESET}_4") (pintype "bidirectional"))
    )
    (net (code "55") (name "unconnected-(IC2-NC-Pad9)") (class "Default")
      (node (ref "IC2") (pin "9") (pinfunction "NC_9") (pintype "no_connect"))
    )
    (net (code "56") (name "unconnected-(U$1-23{slash}USB_DP-Pad12)") (class "Default")
      (node (ref "U$1") (pin "12") (pinfunction "23/USB_DP_12") (pintype "bidirectional"))
    )
    (net (code "57") (name "unconnected-(U$1-24{slash}USB_DM-Pad13)") (class "Default")
      (node (ref "U$1") (pin "13") (pinfunction "24/USB_DM_13") (pintype "bidirectional"))
    )
    (net (code "58") (name "unconnected-(U$1-VBAT-Pad38)") (class "Default")
      (node (ref "U$1") (pin "38") (pinfunction "VBAT_38") (pintype "bidirectional"))
    )
    (net (code "59") (name "unconnected-(U$2-PadRING_SW)") (class "Default")
      (node (ref "U$2") (pin "RING_SW") (pinfunction "RING_SW_RING_SW") (pintype "bidirectional"))
    )
    (net (code "60") (name "unconnected-(WLAN-PadRST)") (class "Default")
      (node (ref "WLAN") (pin "RST") (pinfunction "RST_RST") (pintype "bidirectional"))
    )
  )
)
